# rfid_accessctl.net
KiCad netlist of a schematic drawn in EAGLE
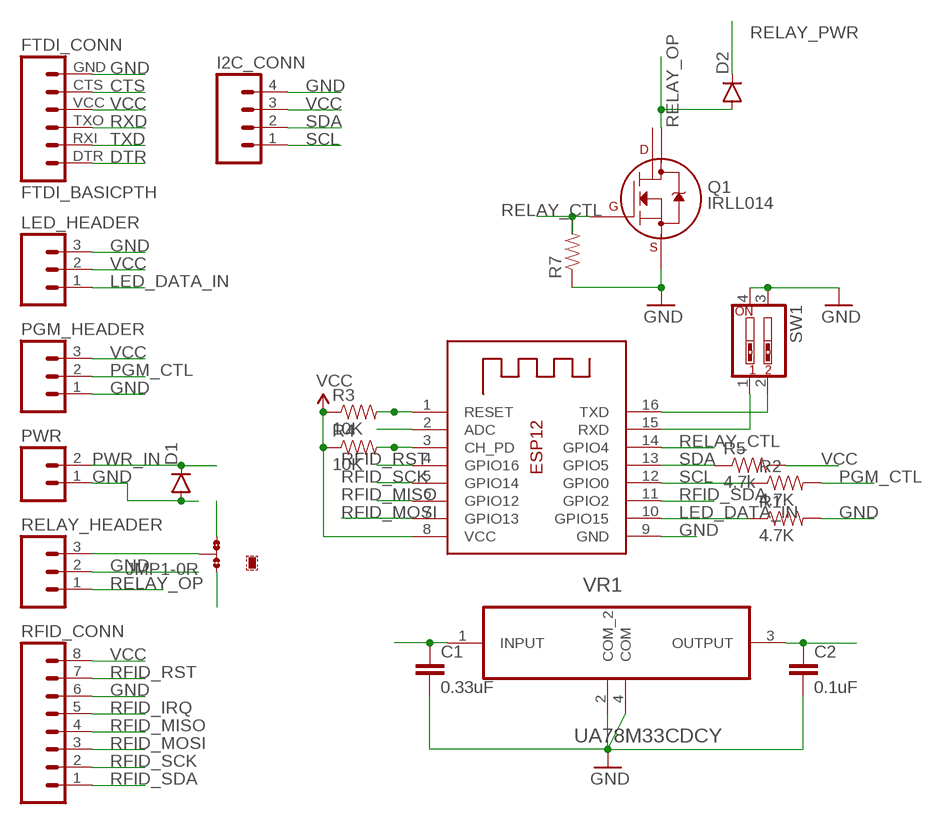
[diagram p0: schematic, sheet 1]

(export (version "E")
  (design (tool "Eeschema 10.0.6"))
  (components
    (comp (ref "C1")
      (value "0.33uF")
      (footprint "eagle-import:0805")
      (libsource (lib "eagle-import") (part "CAP0805"))
    )
    (comp (ref "C2")
      (value "0.1uF")
      (footprint "eagle-import:0805")
      (libsource (lib "eagle-import") (part "CAP0805"))
    )
    (comp (ref "D1")
      (value "DIODESMA")
      (footprint "eagle-import:SMA-DIODE")
      (libsource (lib "eagle-import") (part "DIODESMA"))
    )
    (comp (ref "D2")
      (value "DIODESMA")
      (footprint "eagle-import:SMA-DIODE")
      (libsource (lib "eagle-import") (part "DIODESMA"))
    )
    (comp (ref "FTDI_CONN")
      (value "FTDI_BASICPTH")
      (footprint "eagle-import:FTDI_BASIC")
      (libsource (lib "eagle-import") (part "FTDI_BASICPTH"))
    )
    (comp (ref "I2C_CONN")
      (value "M04PTH")
      (footprint "eagle-import:1X04")
      (libsource (lib "eagle-import") (part "M04PTH"))
    )
    (comp (ref "JMP1")
      (value "0R-JUMPB")
      (footprint "eagle-import:B0R-JMP")
      (libsource (lib "eagle-import") (part "0R-JUMPB"))
    )
    (comp (ref "LED_HEADER")
      (value "M03PTH")
      (footprint "eagle-import:1X03")
      (libsource (lib "eagle-import") (part "M03PTH"))
    )
    (comp (ref "PGM_HEADER")
      (value "M03PTH")
      (footprint "eagle-import:1X03")
      (libsource (lib "eagle-import") (part "M03PTH"))
    )
    (comp (ref "PWR")
      (value "M02PTH")
      (footprint "eagle-import:1X02")
      (libsource (lib "eagle-import") (part "M02PTH"))
    )
    (comp (ref "Q1")
      (value "IRLL014")
      (footprint "eagle-import:SOT-223")
      (libsource (lib "eagle-import") (part "IRLL014"))
    )
    (comp (ref "R1")
      (value "4.7K")
      (footprint "eagle-import:0603-RES")
      (libsource (lib "eagle-import") (part "10KOHM-1/10W-1%(0603)0603"))
    )
    (comp (ref "R2")
      (value "4.7K")
      (footprint "eagle-import:0603-RES")
      (libsource (lib "eagle-import") (part "10KOHM-1/10W-1%(0603)0603"))
    )
    (comp (ref "R3")
      (value "10K")
      (footprint "eagle-import:0603-RES")
      (libsource (lib "eagle-import") (part "10KOHM-1/10W-1%(0603)0603"))
    )
    (comp (ref "R4")
      (value "10K")
      (footprint "eagle-import:0603-RES")
      (libsource (lib "eagle-import") (part "10KOHM-1/10W-1%(0603)0603"))
    )
    (comp (ref "R5")
      (value "4.7k")
      (footprint "eagle-import:0603-RES")
      (libsource (lib "eagle-import") (part "470OHM1/10W1%(0603)"))
    )
    (comp (ref "R7")
      (value "RESISTOR0603-RES")
      (footprint "eagle-import:0603-RES")
      (libsource (lib "eagle-import") (part "RESISTOR0603-RES"))
    )
    (comp (ref "RELAY_HEADER")
      (value "M03PTH")
      (footprint "eagle-import:1X03")
      (libsource (lib "eagle-import") (part "M03PTH"))
    )
    (comp (ref "RFID_CONN")
      (value "M08")
      (footprint "eagle-import:1X08_ROUND")
      (libsource (lib "eagle-import") (part "M08"))
    )
    (comp (ref "SW1")
      (value "SW_DIP-2-SMT-HALFSIZE")
      (footprint "eagle-import:DIPSWITCH-02-50MIL")
      (libsource (lib "eagle-import") (part "SW_DIP-2-SMT-HALFSIZE"))
    )
    (comp (ref "VR1")
      (value "UA78M33CDCY")
      (footprint "eagle-import:SOT230P700X180-4N")
      (libsource (lib "eagle-import") (part "UA78M33CDCY"))
    )
    (comp (ref "X1")
      (value "ESP-12")
      (footprint "eagle-import:ESP-12")
      (libsource (lib "eagle-import") (part "ESP-12"))
    )
  )
  (nets
    (net (code "1") (name "/CTS") (class "Default")
      (node (ref "FTDI_CONN") (pin "CTS") (pinfunction "5_CTS") (pintype "passive"))
    )
    (net (code "2") (name "/DTR") (class "Default")
      (node (ref "FTDI_CONN") (pin "DTR") (pinfunction "1_DTR") (pintype "passive"))
    )
    (net (code "3") (name "/LED_DATA_IN") (class "Default")
      (node (ref "LED_HEADER") (pin "1") (pinfunction "1_1") (pintype "passive"))
      (node (ref "R1") (pin "1") (pinfunction "1_1") (pintype "passive"))
      (node (ref "X1") (pin "10") (pinfunction "GPIO15_10") (pintype "bidirectional"))
    )
    (net (code "4") (name "/PGM_CTL") (class "Default")
      (node (ref "PGM_HEADER") (pin "2") (pinfunction "2_2") (pintype "passive"))
      (node (ref "R2") (pin "2") (pinfunction "2_2") (pintype "passive"))
    )
    (net (code "5") (name "/PWR_IN") (class "Default")
      (node (ref "C1") (pin "1") (pinfunction "1_1") (pintype "passive"))
      (node (ref "D1") (pin "C") (pinfunction "C_C") (pintype "passive"))
      (node (ref "JMP1") (pin "3") (pinfunction "3_3") (pintype "passive"))
      (node (ref "PWR") (pin "2") (pinfunction "2_2") (pintype "passive"))
      (node (ref "VR1") (pin "1") (pinfunction "INPUT_1") (pintype "input"))
    )
    (net (code "6") (name "/RELAY_CTL") (class "Default")
      (node (ref "Q1") (pin "1") (pinfunction "G_1") (pintype "tri_state"))
      (node (ref "R7") (pin "2") (pinfunction "2_2") (pintype "passive"))
      (node (ref "X1") (pin "14") (pinfunction "GPIO4_14") (pintype "bidirectional"))
    )
    (net (code "7") (name "/RELAY_OP") (class "Default")
      (node (ref "D2") (pin "A") (pinfunction "A_A") (pintype "passive"))
      (node (ref "Q1") (pin "2") (pinfunction "D1_2") (pintype "bidirectional"))
      (node (ref "RELAY_HEADER") (pin "1") (pinfunction "1_1") (pintype "passive"))
    )
    (net (code "8") (name "/RELAY_PWR") (class "Default")
      (node (ref "D2") (pin "C") (pinfunction "C_C") (pintype "passive"))
      (node (ref "JMP1") (pin "2") (pinfunction "2_2") (pintype "passive"))
      (node (ref "RELAY_HEADER") (pin "3") (pinfunction "3_3") (pintype "passive"))
    )
    (net (code "9") (name "/RFID_IRQ") (class "Default")
      (node (ref "RFID_CONN") (pin "5") (pinfunction "5_5") (pintype "passive"))
    )
    (net (code "10") (name "/RFID_MISO") (class "Default")
      (node (ref "RFID_CONN") (pin "4") (pinfunction "4_4") (pintype "passive"))
      (node (ref "X1") (pin "6") (pinfunction "GPIO12_6") (pintype "bidirectional"))
    )
    (net (code "11") (name "/RFID_MOSI") (class "Default")
      (node (ref "RFID_CONN") (pin "3") (pinfunction "3_3") (pintype "passive"))
      (node (ref "X1") (pin "7") (pinfunction "GPIO13_7") (pintype "bidirectional"))
    )
    (net (code "12") (name "/RFID_RST") (class "Default")
      (node (ref "RFID_CONN") (pin "7") (pinfunction "7_7") (pintype "passive"))
      (node (ref "X1") (pin "4") (pinfunction "GPIO16_4") (pintype "bidirectional"))
    )
    (net (code "13") (name "/RFID_SCK") (class "Default")
      (node (ref "RFID_CONN") (pin "2") (pinfunction "2_2") (pintype "passive"))
      (node (ref "X1") (pin "5") (pinfunction "GPIO14_5") (pintype "bidirectional"))
    )
    (net (code "14") (name "/RFID_SDA") (class "Default")
      (node (ref "RFID_CONN") (pin "1") (pinfunction "1_1") (pintype "passive"))
      (node (ref "X1") (pin "11") (pinfunction "GPIO2_11") (pintype "bidirectional"))
    )
    (net (code "15") (name "/RXD") (class "Default")
      (node (ref "FTDI_CONN") (pin "TXO") (pinfunction "3_TXO") (pintype "passive"))
      (node (ref "SW1") (pin "1") (pinfunction "1_1") (pintype "passive"))
      (node (ref "X1") (pin "15") (pinfunction "RXD_15") (pintype "input"))
    )
    (net (code "16") (name "/SCL") (class "Default")
      (node (ref "I2C_CONN") (pin "1") (pinfunction "1_1") (pintype "passive"))
      (node (ref "R2") (pin "1") (pinfunction "1_1") (pintype "passive"))
      (node (ref "X1") (pin "12") (pinfunction "GPIO0_12") (pintype "bidirectional"))
    )
    (net (code "17") (name "/SDA") (class "Default")
      (node (ref "I2C_CONN") (pin "2") (pinfunction "2_2") (pintype "passive"))
      (node (ref "R5") (pin "1") (pinfunction "1_1") (pintype "passive"))
      (node (ref "X1") (pin "13") (pinfunction "GPIO5_13") (pintype "bidirectional"))
    )
    (net (code "18") (name "/TXD") (class "Default")
      (node (ref "FTDI_CONN") (pin "RXI") (pinfunction "2_RXI") (pintype "passive"))
      (node (ref "SW1") (pin "2") (pinfunction "2_2") (pintype "passive"))
      (node (ref "X1") (pin "16") (pinfunction "TXD_16") (pintype "output"))
    )
    (net (code "19") (name "GND") (class "Default")
      (node (ref "C1") (pin "2") (pinfunction "2_2") (pintype "passive"))
      (node (ref "C2") (pin "2") (pinfunction "2_2") (pintype "passive"))
      (node (ref "D1") (pin "A") (pinfunction "A_A") (pintype "passive"))
      (node (ref "FTDI_CONN") (pin "GND") (pinfunction "6_GND") (pintype "passive"))
      (node (ref "I2C_CONN") (pin "4") (pinfunction "4_4") (pintype "passive"))
      (node (ref "LED_HEADER") (pin "3") (pinfunction "3_3") (pintype "passive"))
      (node (ref "PGM_HEADER") (pin "1") (pinfunction "1_1") (pintype "passive"))
      (node (ref "PWR") (pin "1") (pinfunction "1_1") (pintype "passive"))
      (node (ref "Q1") (pin "3") (pinfunction "S_3") (pintype "bidirectional"))
      (node (ref "R1") (pin "2") (pinfunction "2_2") (pintype "passive"))
      (node (ref "R7") (pin "1") (pinfunction "1_1") (pintype "passive"))
      (node (ref "RELAY_HEADER") (pin "2") (pinfunction "2_2") (pintype "passive"))
      (node (ref "RFID_CONN") (pin "6") (pinfunction "6_6") (pintype "passive"))
      (node (ref "SW1") (pin "3") (pinfunction "3_3") (pintype "passive"))
      (node (ref "SW1") (pin "4") (pinfunction "4_4") (pintype "passive"))
      (node (ref "VR1") (pin "2") (pinfunction "COM_2_2") (pintype "passive"))
      (node (ref "VR1") (pin "4") (pinfunction "COM_4") (pintype "passive"))
      (node (ref "X1") (pin "9") (pinfunction "GND_9") (pintype "power_in"))
    )
    (net (code "20") (name "Net-(X1-CH_PD)") (class "Default")
      (node (ref "R4") (pin "2") (pinfunction "2_2") (pintype "passive"))
      (node (ref "X1") (pin "3") (pinfunction "CH_PD_3") (pintype "input"))
    )
    (net (code "21") (name "Net-(X1-RESET)") (class "Default")
      (node (ref "R3") (pin "2") (pinfunction "2_2") (pintype "passive"))
      (node (ref "X1") (pin "1") (pinfunction "RESET_1") (pintype "input"))
    )
    (net (code "22") (name "VCC") (class "Default")
      (node (ref "C2") (pin "1") (pinfunction "1_1") (pintype "passive"))
      (node (ref "FTDI_CONN") (pin "VCC") (pinfunction "4_VCC") (pintype "passive"))
      (node (ref "I2C_CONN") (pin "3") (pinfunction "3_3") (pintype "passive"))
      (node (ref "JMP1") (pin "1") (pinfunction "1_1") (pintype "passive"))
      (node (ref "LED_HEADER") (pin "2") (pinfunction "2_2") (pintype "passive"))
      (node (ref "PGM_HEADER") (pin "3") (pinfunction "3_3") (pintype "passive"))
      (node (ref "R3") (pin "1") (pinfunction "1_1") (pintype "passive"))
      (node (ref "R4") (pin "1") (pinfunction "1_1") (pintype "passive"))
      (node (ref "R5") (pin "2") (pinfunction "2_2") (pintype "passive"))
      (node (ref "RFID_CONN") (pin "8") (pinfunction "8_8") (pintype "passive"))
      (node (ref "VR1") (pin "3") (pinfunction "OUTPUT_3") (pintype "output"))
      (node (ref "X1") (pin "8") (pinfunction "VCC_8") (pintype "power_in"))
    )
    (net (code "23") (name "unconnected-(Q1-D2-Pad4)") (class "Default")
      (node (ref "Q1") (pin "4") (pinfunction "D2_4") (pintype "bidirectional"))
    )
    (net (code "24") (name "unconnected-(X1-ADC-Pad2)") (class "Default")
      (node (ref "X1") (pin "2") (pinfunction "ADC_2") (pintype "passive"))
    )
  )
)
